# thar_board_land_mk1.net
KiCad netlist of a schematic drawn in EAGLE
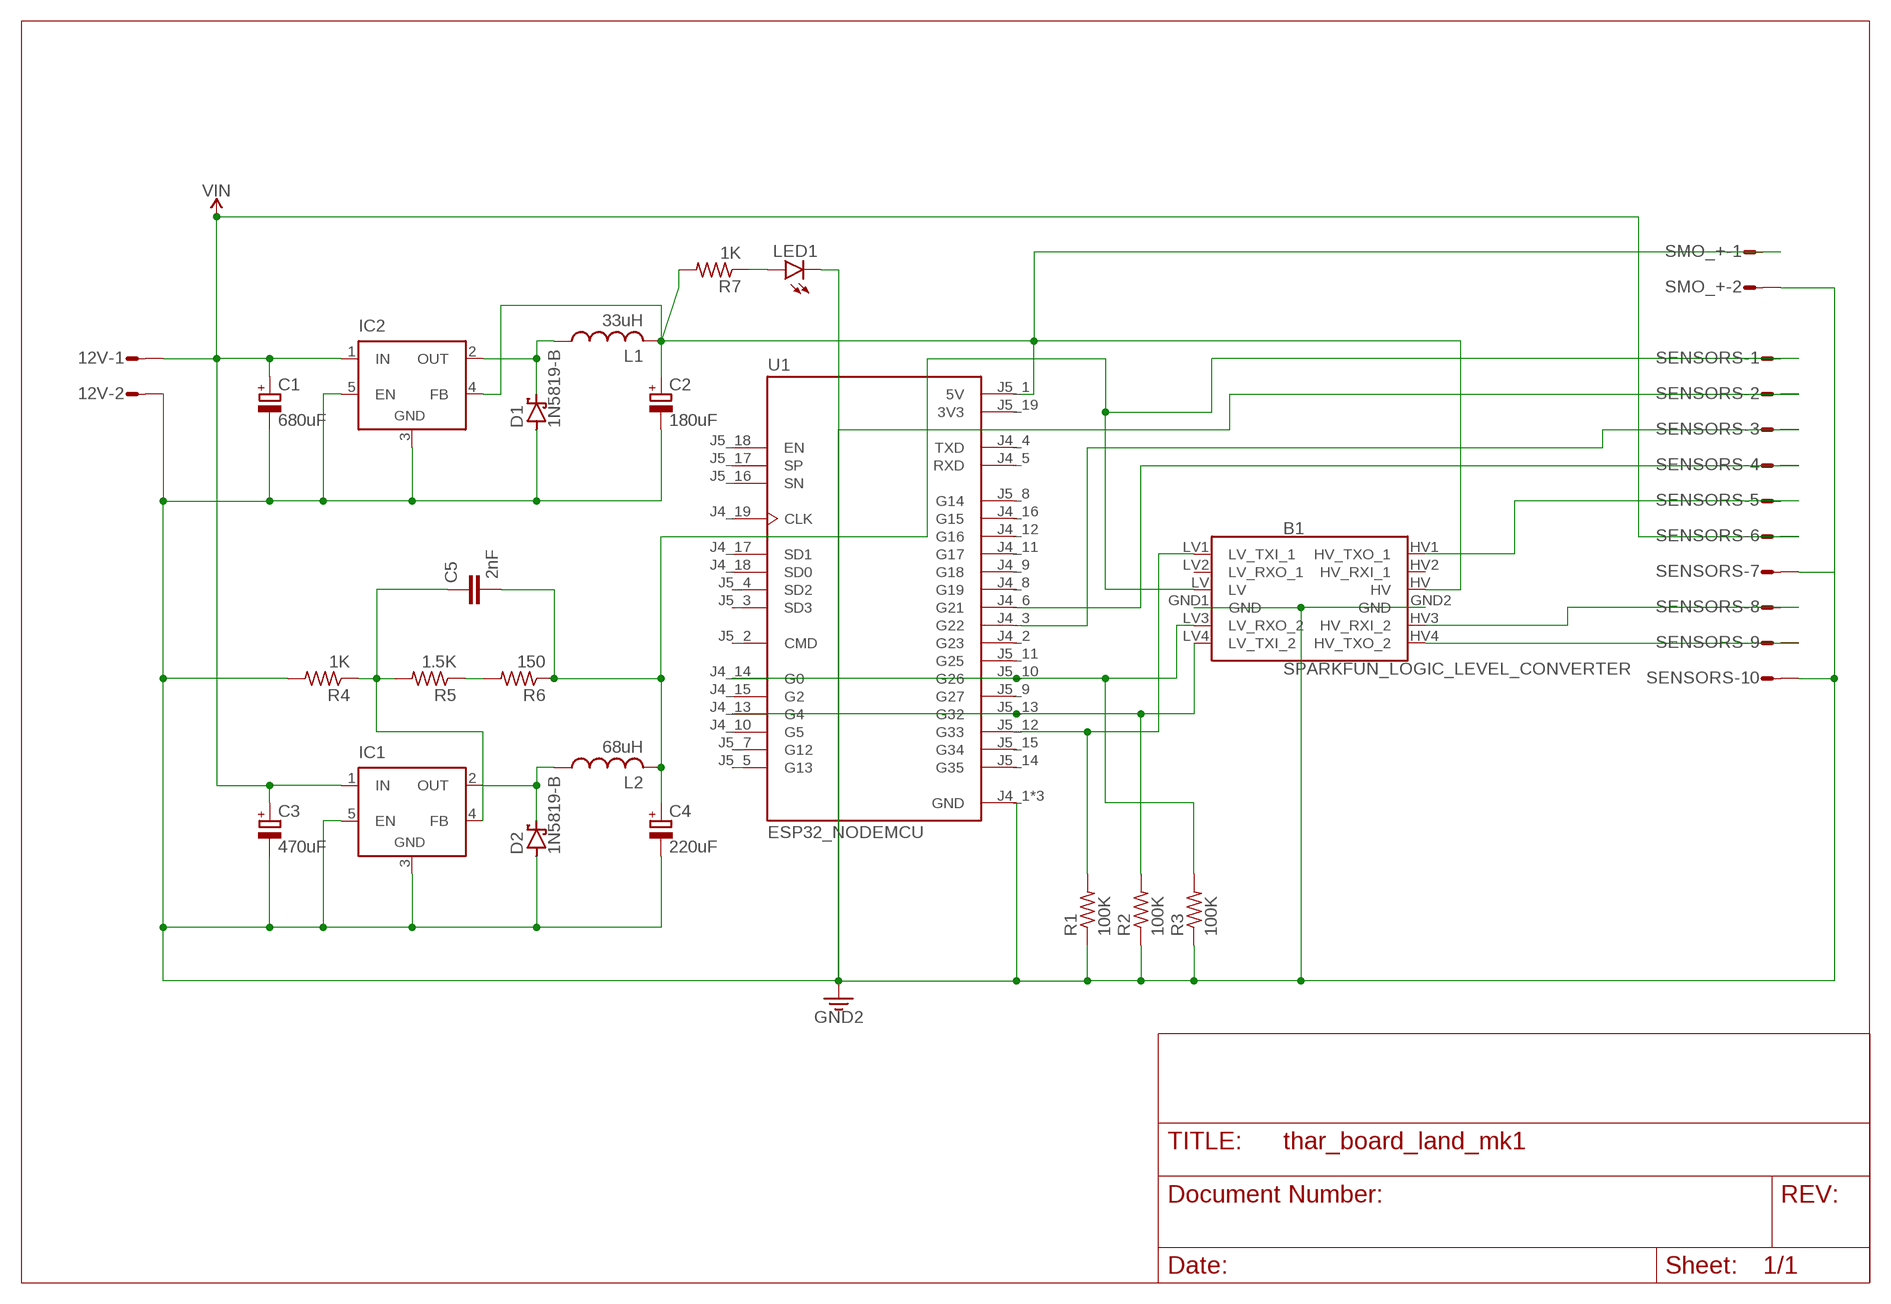
[diagram p0: schematic, sheet 1]

(export (version "E")
  (design (tool "Eeschema 10.0.6"))
  (components
    (comp (ref "12V")
      (value "L02P")
      (footprint "eagle-import:L02P")
      (libsource (lib "eagle-import") (part "L02P"))
    )
    (comp (ref "B1")
      (value "SPARKFUN_LOGIC_LEVEL_CONVERTER")
      (footprint "eagle-import:SPARKFUN_LOGIC_LEVEL_CONVERTER")
      (libsource (lib "eagle-import") (part "SPARKFUN_LOGIC_LEVEL_CONVERTER"))
    )
    (comp (ref "C1")
      (value "680uF")
      (footprint "eagle-import:E2,5-7")
      (libsource (lib "eagle-import") (part "CPOL-EUE2.5-7"))
    )
    (comp (ref "C2")
      (value "180uF")
      (footprint "eagle-import:E2,5-7")
      (libsource (lib "eagle-import") (part "CPOL-EUE2.5-7"))
    )
    (comp (ref "C3")
      (value "470uF")
      (footprint "eagle-import:E2,5-7")
      (libsource (lib "eagle-import") (part "CPOL-EUE2.5-7"))
    )
    (comp (ref "C4")
      (value "220uF")
      (footprint "eagle-import:E2,5-7")
      (libsource (lib "eagle-import") (part "CPOL-EUE2.5-7"))
    )
    (comp (ref "C5")
      (value "2nF")
      (footprint "eagle-import:C025-025X050")
      (libsource (lib "eagle-import") (part "C-EU025-025X050"))
    )
    (comp (ref "D1")
      (value "1N5819-B")
      (footprint "eagle-import:DO41-7.6")
      (libsource (lib "eagle-import") (part "1N5819-B"))
    )
    (comp (ref "D2")
      (value "1N5819-B")
      (footprint "eagle-import:DO41-7.6")
      (libsource (lib "eagle-import") (part "1N5819-B"))
    )
    (comp (ref "IC1")
      (value "LM2596TH")
      (footprint "eagle-import:TO220-52")
      (libsource (lib "eagle-import") (part "LM2596TH"))
    )
    (comp (ref "IC2")
      (value "LM2596TH")
      (footprint "eagle-import:TO220-52")
      (libsource (lib "eagle-import") (part "LM2596TH"))
    )
    (comp (ref "L1")
      (value "33uH")
      (footprint "eagle-import:TFI0410")
      (libsource (lib "eagle-import") (part "L-USTFI0410"))
    )
    (comp (ref "L2")
      (value "68uH")
      (footprint "eagle-import:TFI0410")
      (libsource (lib "eagle-import") (part "L-USTFI0410"))
    )
    (comp (ref "LED1")
      (value "LED3MM")
      (footprint "eagle-import:LED3MM")
      (libsource (lib "eagle-import") (part "LED3MM"))
    )
    (comp (ref "R1")
      (value "100K")
      (footprint "eagle-import:0207_10")
      (libsource (lib "eagle-import") (part "R-US_0207/10"))
    )
    (comp (ref "R2")
      (value "100K")
      (footprint "eagle-import:0207_10")
      (libsource (lib "eagle-import") (part "R-US_0207/10"))
    )
    (comp (ref "R3")
      (value "100K")
      (footprint "eagle-import:0207_10")
      (libsource (lib "eagle-import") (part "R-US_0207/10"))
    )
    (comp (ref "R4")
      (value "1K")
      (footprint "eagle-import:0207_10")
      (libsource (lib "eagle-import") (part "R-US_0207/10"))
    )
    (comp (ref "R5")
      (value "1.5K")
      (footprint "eagle-import:0207_10")
      (libsource (lib "eagle-import") (part "R-US_0207/10"))
    )
    (comp (ref "R6")
      (value "150")
      (footprint "eagle-import:0207_10")
      (libsource (lib "eagle-import") (part "R-US_0207/10"))
    )
    (comp (ref "R7")
      (value "1K")
      (footprint "eagle-import:0207_10")
      (libsource (lib "eagle-import") (part "R-US_0207/10"))
    )
    (comp (ref "SENSORS")
      (value "L10P")
      (footprint "eagle-import:L10P")
      (libsource (lib "eagle-import") (part "L10P"))
    )
    (comp (ref "SMO_+")
      (value "L02P")
      (footprint "eagle-import:L02P")
      (libsource (lib "eagle-import") (part "L02P"))
    )
    (comp (ref "U1")
      (value "ESP32_NODEMCU")
      (footprint "eagle-import:MODULE_ESP32_NODEMCU")
      (fields (field (name "MF") "Espressif Systems") (field (name "MP") "ESP32 NodeMCU"))
      (libsource (lib "eagle-import") (part "ESP32_NODEMCU"))
    )
  )
  (nets
    (net (code "1") (name "/3V3") (class "Default")
      (node (ref "U1") (pin "J5_19") (pinfunction "3V3_J5_19") (pintype "power_in"))
    )
    (net (code "2") (name "GND2") (class "Default")
      (node (ref "12V") (pin "2") (pinfunction "S_2") (pintype "passive"))
      (node (ref "B1") (pin "GND1") (pinfunction "GND_GND1") (pintype "power_in"))
      (node (ref "B1") (pin "GND2") (pinfunction "GND_GND2") (pintype "power_in"))
      (node (ref "C1") (pin "-") (pinfunction "-_-") (pintype "passive"))
      (node (ref "C2") (pin "-") (pinfunction "-_-") (pintype "passive"))
      (node (ref "C3") (pin "-") (pinfunction "-_-") (pintype "passive"))
      (node (ref "C4") (pin "-") (pinfunction "-_-") (pintype "passive"))
      (node (ref "D1") (pin "A") (pinfunction "A_A") (pintype "passive"))
      (node (ref "D2") (pin "A") (pinfunction "A_A") (pintype "passive"))
      (node (ref "IC1") (pin "3") (pinfunction "GND_3") (pintype "power_in"))
      (node (ref "IC1") (pin "5") (pinfunction "EN_5") (pintype "input"))
      (node (ref "IC2") (pin "3") (pinfunction "GND_3") (pintype "power_in"))
      (node (ref "IC2") (pin "5") (pinfunction "EN_5") (pintype "input"))
      (node (ref "LED1") (pin "K") (pinfunction "C_K") (pintype "passive"))
      (node (ref "R1") (pin "1") (pinfunction "1_1") (pintype "passive"))
      (node (ref "R2") (pin "1") (pinfunction "1_1") (pintype "passive"))
      (node (ref "R3") (pin "1") (pinfunction "1_1") (pintype "passive"))
      (node (ref "R4") (pin "2") (pinfunction "2_2") (pintype "passive"))
      (node (ref "SENSORS") (pin "10") (pinfunction "S_10") (pintype "passive"))
      (node (ref "SENSORS") (pin "2") (pinfunction "S_2") (pintype "passive"))
      (node (ref "SENSORS") (pin "7") (pinfunction "S_7") (pintype "passive"))
      (node (ref "SMO_+") (pin "2") (pinfunction "S_2") (pintype "passive"))
      (node (ref "U1") (pin "J4_1") (pinfunction "GND_J4_1") (pintype "power_in"))
      (node (ref "U1") (pin "J4_7") (pinfunction "GND_J4_7") (pintype "power_in"))
      (node (ref "U1") (pin "J5_6") (pinfunction "GND_J5_6") (pintype "power_in"))
    )
    (net (code "3") (name "Net-(B1-HV_RXI_2)") (class "Default")
      (node (ref "B1") (pin "HV3") (pinfunction "HV_RXI_2_HV3") (pintype "bidirectional"))
      (node (ref "SENSORS") (pin "8") (pinfunction "S_8") (pintype "passive"))
    )
    (net (code "4") (name "Net-(B1-HV_TXO_1)") (class "Default")
      (node (ref "B1") (pin "HV1") (pinfunction "HV_TXO_1_HV1") (pintype "bidirectional"))
      (node (ref "SENSORS") (pin "5") (pinfunction "S_5") (pintype "passive"))
    )
    (net (code "5") (name "Net-(B1-HV_TXO_2)") (class "Default")
      (node (ref "B1") (pin "HV4") (pinfunction "HV_TXO_2_HV4") (pintype "bidirectional"))
      (node (ref "SENSORS") (pin "9") (pinfunction "S_9") (pintype "passive"))
    )
    (net (code "6") (name "Net-(B1-LV_RXO_2)") (class "Default")
      (node (ref "B1") (pin "LV3") (pinfunction "LV_RXO_2_LV3") (pintype "bidirectional"))
      (node (ref "R3") (pin "2") (pinfunction "2_2") (pintype "passive"))
      (node (ref "U1") (pin "J4_14") (pinfunction "G0_J4_14") (pintype "bidirectional"))
      (node (ref "U1") (pin "J5_10") (pinfunction "G26_J5_10") (pintype "bidirectional"))
    )
    (net (code "7") (name "Net-(B1-LV_TXI_1)") (class "Default")
      (node (ref "B1") (pin "LV1") (pinfunction "LV_TXI_1_LV1") (pintype "bidirectional"))
      (node (ref "R1") (pin "2") (pinfunction "2_2") (pintype "passive"))
      (node (ref "U1") (pin "J5_12") (pinfunction "G33_J5_12") (pintype "bidirectional"))
    )
    (net (code "8") (name "Net-(B1-LV_TXI_2)") (class "Default")
      (node (ref "B1") (pin "LV4") (pinfunction "LV_TXI_2_LV4") (pintype "bidirectional"))
      (node (ref "R2") (pin "2") (pinfunction "2_2") (pintype "passive"))
      (node (ref "U1") (pin "J4_13") (pinfunction "G4_J4_13") (pintype "bidirectional"))
      (node (ref "U1") (pin "J5_13") (pinfunction "G32_J5_13") (pintype "bidirectional"))
    )
    (net (code "9") (name "Net-(IC1-FB)") (class "Default")
      (node (ref "C5") (pin "1") (pinfunction "1_1") (pintype "passive"))
      (node (ref "IC1") (pin "4") (pinfunction "FB_4") (pintype "input"))
      (node (ref "R4") (pin "1") (pinfunction "1_1") (pintype "passive"))
      (node (ref "R5") (pin "2") (pinfunction "2_2") (pintype "passive"))
    )
    (net (code "10") (name "Net-(IC1-OUT)") (class "Default")
      (node (ref "D2") (pin "C") (pinfunction "C_C") (pintype "passive"))
      (node (ref "IC1") (pin "2") (pinfunction "OUT_2") (pintype "output"))
      (node (ref "L2") (pin "1") (pinfunction "1_1") (pintype "passive"))
    )
    (net (code "11") (name "Net-(IC2-FB)") (class "Default")
      (node (ref "B1") (pin "HV") (pinfunction "HV_HV") (pintype "power_in"))
      (node (ref "C2") (pin "+") (pinfunction "+_+") (pintype "passive"))
      (node (ref "IC2") (pin "4") (pinfunction "FB_4") (pintype "input"))
      (node (ref "L1") (pin "2") (pinfunction "2_2") (pintype "passive"))
      (node (ref "R7") (pin "2") (pinfunction "2_2") (pintype "passive"))
      (node (ref "SMO_+") (pin "1") (pinfunction "S_1") (pintype "passive"))
      (node (ref "U1") (pin "J5_1") (pinfunction "5V_J5_1") (pintype "power_in"))
    )
    (net (code "12") (name "Net-(IC2-OUT)") (class "Default")
      (node (ref "D1") (pin "C") (pinfunction "C_C") (pintype "passive"))
      (node (ref "IC2") (pin "2") (pinfunction "OUT_2") (pintype "output"))
      (node (ref "L1") (pin "1") (pinfunction "1_1") (pintype "passive"))
    )
    (net (code "13") (name "Net-(LED1-PadA)") (class "Default")
      (node (ref "LED1") (pin "A") (pinfunction "A_A") (pintype "passive"))
      (node (ref "R7") (pin "1") (pinfunction "1_1") (pintype "passive"))
    )
    (net (code "14") (name "Net-(R5-Pad1)") (class "Default")
      (node (ref "R5") (pin "1") (pinfunction "1_1") (pintype "passive"))
      (node (ref "R6") (pin "2") (pinfunction "2_2") (pintype "passive"))
    )
    (net (code "15") (name "Net-(SENSORSA-S)") (class "Default")
      (node (ref "B1") (pin "LV") (pinfunction "LV_LV") (pintype "power_in"))
      (node (ref "C4") (pin "+") (pinfunction "+_+") (pintype "passive"))
      (node (ref "C5") (pin "2") (pinfunction "2_2") (pintype "passive"))
      (node (ref "L2") (pin "2") (pinfunction "2_2") (pintype "passive"))
      (node (ref "R6") (pin "1") (pinfunction "1_1") (pintype "passive"))
      (node (ref "SENSORS") (pin "1") (pinfunction "S_1") (pintype "passive"))
    )
    (net (code "16") (name "Net-(SENSORSD-S)") (class "Default")
      (node (ref "SENSORS") (pin "3") (pinfunction "S_3") (pintype "passive"))
      (node (ref "U1") (pin "J4_3") (pinfunction "G22_J4_3") (pintype "bidirectional"))
    )
    (net (code "17") (name "Net-(SENSORSE-S)") (class "Default")
      (node (ref "SENSORS") (pin "4") (pinfunction "S_4") (pintype "passive"))
      (node (ref "U1") (pin "J4_6") (pinfunction "G21_J4_6") (pintype "bidirectional"))
    )
    (net (code "18") (name "VIN") (class "Default")
      (node (ref "12V") (pin "1") (pinfunction "S_1") (pintype "passive"))
      (node (ref "C1") (pin "+") (pinfunction "+_+") (pintype "passive"))
      (node (ref "C3") (pin "+") (pinfunction "+_+") (pintype "passive"))
      (node (ref "IC1") (pin "1") (pinfunction "IN_1") (pintype "input"))
      (node (ref "IC2") (pin "1") (pinfunction "IN_1") (pintype "input"))
      (node (ref "SENSORS") (pin "6") (pinfunction "S_6") (pintype "passive"))
    )
    (net (code "19") (name "unconnected-(B1-HV_RXI_1-PadHV2)") (class "Default")
      (node (ref "B1") (pin "HV2") (pinfunction "HV_RXI_1_HV2") (pintype "bidirectional"))
    )
    (net (code "20") (name "unconnected-(B1-LV_RXO_1-PadLV2)") (class "Default")
      (node (ref "B1") (pin "LV2") (pinfunction "LV_RXO_1_LV2") (pintype "bidirectional"))
    )
    (net (code "21") (name "unconnected-(U1-CLK-PadJ4_19)") (class "Default")
      (node (ref "U1") (pin "J4_19") (pinfunction "CLK_J4_19") (pintype "input"))
    )
    (net (code "22") (name "unconnected-(U1-CMD-PadJ5_2)") (class "Default")
      (node (ref "U1") (pin "J5_2") (pinfunction "CMD_J5_2") (pintype "bidirectional"))
    )
    (net (code "23") (name "unconnected-(U1-EN-PadJ5_18)") (class "Default")
      (node (ref "U1") (pin "J5_18") (pinfunction "EN_J5_18") (pintype "input"))
    )
    (net (code "24") (name "unconnected-(U1-G2-PadJ4_15)") (class "Default")
      (node (ref "U1") (pin "J4_15") (pinfunction "G2_J4_15") (pintype "bidirectional"))
    )
    (net (code "25") (name "unconnected-(U1-G5-PadJ4_10)") (class "Default")
      (node (ref "U1") (pin "J4_10") (pinfunction "G5_J4_10") (pintype "bidirectional"))
    )
    (net (code "26") (name "unconnected-(U1-G12-PadJ5_7)") (class "Default")
      (node (ref "U1") (pin "J5_7") (pinfunction "G12_J5_7") (pintype "bidirectional"))
    )
    (net (code "27") (name "unconnected-(U1-G13-PadJ5_5)") (class "Default")
      (node (ref "U1") (pin "J5_5") (pinfunction "G13_J5_5") (pintype "bidirectional"))
    )
    (net (code "28") (name "unconnected-(U1-G14-PadJ5_8)") (class "Default")
      (node (ref "U1") (pin "J5_8") (pinfunction "G14_J5_8") (pintype "bidirectional"))
    )
    (net (code "29") (name "unconnected-(U1-G15-PadJ4_16)") (class "Default")
      (node (ref "U1") (pin "J4_16") (pinfunction "G15_J4_16") (pintype "bidirectional"))
    )
    (net (code "30") (name "unconnected-(U1-G16-PadJ4_12)") (class "Default")
      (node (ref "U1") (pin "J4_12") (pinfunction "G16_J4_12") (pintype "bidirectional"))
    )
    (net (code "31") (name "unconnected-(U1-G17-PadJ4_11)") (class "Default")
      (node (ref "U1") (pin "J4_11") (pinfunction "G17_J4_11") (pintype "bidirectional"))
    )
    (net (code "32") (name "unconnected-(U1-G18-PadJ4_9)") (class "Default")
      (node (ref "U1") (pin "J4_9") (pinfunction "G18_J4_9") (pintype "bidirectional"))
    )
    (net (code "33") (name "unconnected-(U1-G19-PadJ4_8)") (class "Default")
      (node (ref "U1") (pin "J4_8") (pinfunction "G19_J4_8") (pintype "bidirectional"))
    )
    (net (code "34") (name "unconnected-(U1-G23-PadJ4_2)") (class "Default")
      (node (ref "U1") (pin "J4_2") (pinfunction "G23_J4_2") (pintype "bidirectional"))
    )
    (net (code "35") (name "unconnected-(U1-G25-PadJ5_11)") (class "Default")
      (node (ref "U1") (pin "J5_11") (pinfunction "G25_J5_11") (pintype "bidirectional"))
    )
    (net (code "36") (name "unconnected-(U1-G27-PadJ5_9)") (class "Default")
      (node (ref "U1") (pin "J5_9") (pinfunction "G27_J5_9") (pintype "bidirectional"))
    )
    (net (code "37") (name "unconnected-(U1-G34-PadJ5_15)") (class "Default")
      (node (ref "U1") (pin "J5_15") (pinfunction "G34_J5_15") (pintype "bidirectional"))
    )
    (net (code "38") (name "unconnected-(U1-G35-PadJ5_14)") (class "Default")
      (node (ref "U1") (pin "J5_14") (pinfunction "G35_J5_14") (pintype "bidirectional"))
    )
    (net (code "39") (name "unconnected-(U1-RXD-PadJ4_5)") (class "Default")
      (node (ref "U1") (pin "J4_5") (pinfunction "RXD_J4_5") (pintype "input"))
    )
    (net (code "40") (name "unconnected-(U1-SD0-PadJ4_18)") (class "Default")
      (node (ref "U1") (pin "J4_18") (pinfunction "SD0_J4_18") (pintype "bidirectional"))
    )
    (net (code "41") (name "unconnected-(U1-SD1-PadJ4_17)") (class "Default")
      (node (ref "U1") (pin "J4_17") (pinfunction "SD1_J4_17") (pintype "bidirectional"))
    )
    (net (code "42") (name "unconnected-(U1-SD2-PadJ5_4)") (class "Default")
      (node (ref "U1") (pin "J5_4") (pinfunction "SD2_J5_4") (pintype "bidirectional"))
    )
    (net (code "43") (name "unconnected-(U1-SD3-PadJ5_3)") (class "Default")
      (node (ref "U1") (pin "J5_3") (pinfunction "SD3_J5_3") (pintype "bidirectional"))
    )
    (net (code "44") (name "unconnected-(U1-SN-PadJ5_16)") (class "Default")
      (node (ref "U1") (pin "J5_16") (pinfunction "SN_J5_16") (pintype "input"))
    )
    (net (code "45") (name "unconnected-(U1-SP-PadJ5_17)") (class "Default")
      (node (ref "U1") (pin "J5_17") (pinfunction "SP_J5_17") (pintype "input"))
    )
    (net (code "46") (name "unconnected-(U1-TXD-PadJ4_4)") (class "Default")
      (node (ref "U1") (pin "J4_4") (pinfunction "TXD_J4_4") (pintype "output"))
    )
  )
)
